# OUT.net
KiCad netlist of a schematic drawn in Altium Designer
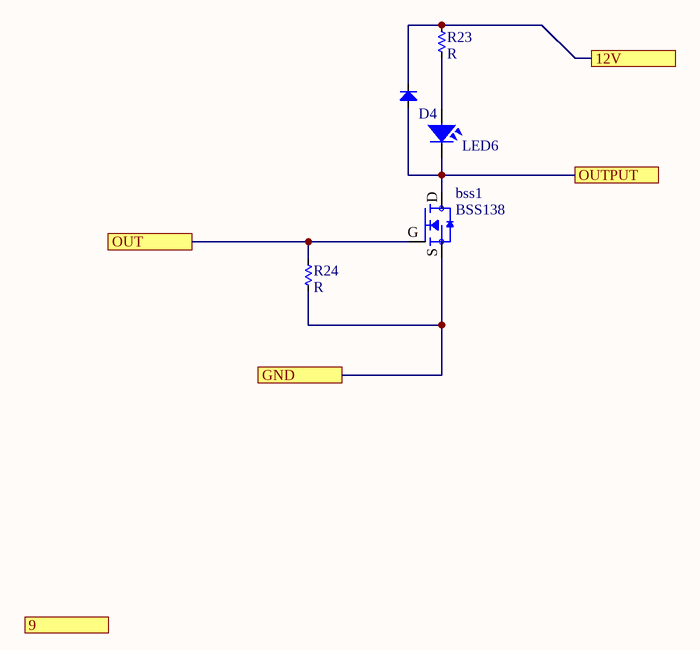
[diagram p0: OUT.SchDoc]

(export (version "E")
  (design (tool "Eeschema 10.0.6"))
  (components
    (comp (ref "bss1")
      (value "BSS138")
      (footprint "SOT23-bss138")
      (description "N-Channel 50V 220mA _Ta_ 360mW _Ta_ Surface Mount Die")
      (fields (field (name "MF") "MICROSS/On Semiconductor"))
      (libsource (lib "nhan") (part "BSS138"))
    )
    (comp (ref "D4")
      (value "Diode")
      (footprint "DIO-SMD-123")
      (description "Default Diode")
      (fields (field (name "PUBLISHER") "Altium Limited"))
      (libsource (lib "nhan") (part "Diode"))
    )
    (comp (ref "LED6") (value "LED") (footprint "LED-0805-Blue") (libsource (lib "LIBRARY") (part "LED SMD")))
    (comp (ref "R23") (value "R") (footprint "RES-SMD-0603_BIG") (libsource (lib "nhan") (part "R")))
    (comp (ref "R24") (value "R") (footprint "RES-SMD-0603_BIG") (libsource (lib "nhan") (part "R")))
  )
  (nets
    (net (code "2") (name "/12V") (class "Default")
      (node (ref "D4") (pin "2") (pinfunction "K_2") (pintype "passive"))
      (node (ref "R23") (pin "1") (pinfunction "1_1") (pintype "passive"))
    )
    (net (code "3") (name "/GND") (class "Default")
      (node (ref "R24") (pin "2") (pinfunction "2_2") (pintype "passive"))
      (node (ref "bss1") (pin "S") (pinfunction "S_S") (pintype "passive"))
    )
    (net (code "4") (name "/OUT") (class "Default")
      (node (ref "R24") (pin "1") (pinfunction "1_1") (pintype "passive"))
      (node (ref "bss1") (pin "G") (pinfunction "G_G") (pintype "passive"))
    )
    (net (code "5") (name "/OUTPUT") (class "Default")
      (node (ref "D4") (pin "1") (pinfunction "A_1") (pintype "passive"))
      (node (ref "LED6") (pin "2") (pinfunction "2_2") (pintype "passive"))
      (node (ref "bss1") (pin "D") (pinfunction "D_D") (pintype "passive"))
    )
    (net (code "6") (name "Net-(LED6-Pad1)") (class "Default")
      (node (ref "LED6") (pin "1") (pinfunction "1_1") (pintype "passive"))
      (node (ref "R23") (pin "2") (pinfunction "2_2") (pintype "passive"))
    )
  )
)
